# Mini-Coil_-_Signal_Board.net
KiCad netlist of a schematic drawn in Altium Designer
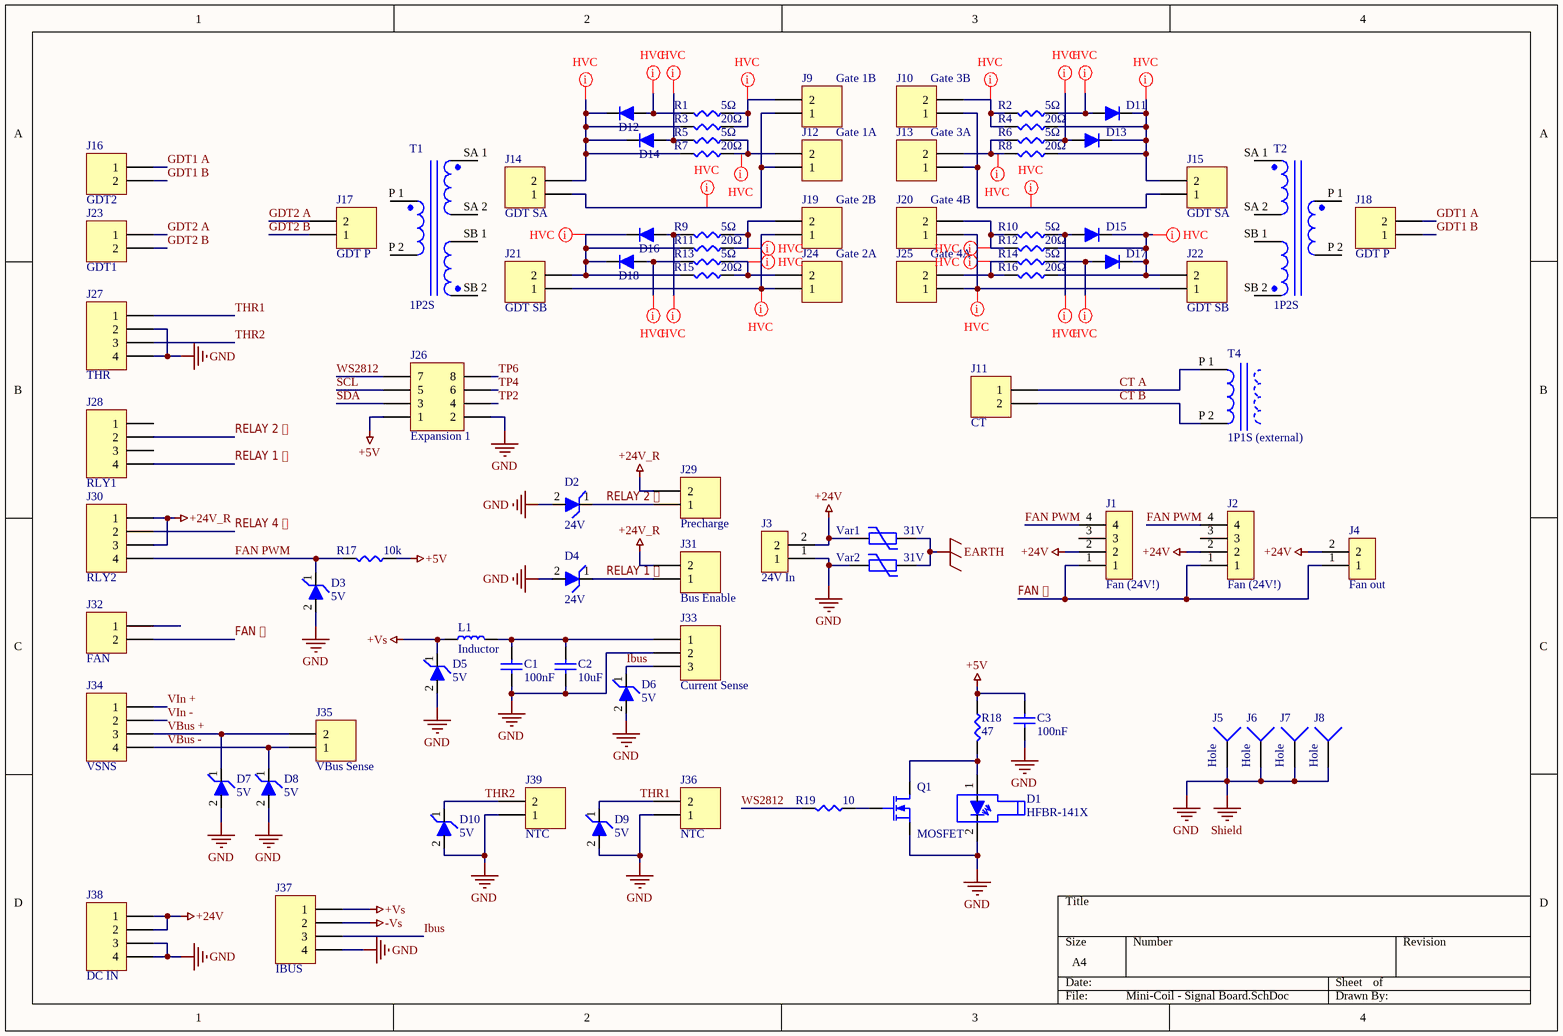
[diagram p0: Mini-Coil - Signal Board.SchDoc]

(export (version "E")
  (design (tool "Eeschema 10.0.6"))
  (components
    (comp (ref "C1") (value "100nF") (footprint "0603") (libsource (lib "stdLib") (part "Cap")))
    (comp (ref "C2") (value "10uF") (footprint "0603") (libsource (lib "stdLib") (part "Cap")))
    (comp (ref "C3") (value "100nF") (footprint "0603") (libsource (lib "stdLib") (part "Cap")))
    (comp (ref "D1")
      (value "HFBR-141X")
      (footprint "HFBR-X5XX")
      (description "Fiber optic transmitter. Click connector")
      (libsource (lib "stdLib") (part "HFBR-15XX Transmitter"))
    )
    (comp (ref "D2") (value "24V") (footprint "DO-214") (libsource (lib "stdLib") (part "TVS Diode")))
    (comp (ref "D3") (value "5V") (footprint "DO-214") (libsource (lib "stdLib") (part "TVS Diode")))
    (comp (ref "D4") (value "24V") (footprint "DO-214") (libsource (lib "stdLib") (part "TVS Diode")))
    (comp (ref "D5") (value "5V") (footprint "DO-214") (libsource (lib "stdLib") (part "TVS Diode")))
    (comp (ref "D6") (value "5V") (footprint "DO-214") (libsource (lib "stdLib") (part "TVS Diode")))
    (comp (ref "D7") (value "5V") (footprint "DO-214") (libsource (lib "stdLib") (part "TVS Diode")))
    (comp (ref "D8") (value "5V") (footprint "DO-214") (libsource (lib "stdLib") (part "TVS Diode")))
    (comp (ref "D9") (value "5V") (footprint "DO-214") (libsource (lib "stdLib") (part "TVS Diode")))
    (comp (ref "D10") (value "5V") (footprint "DO-214") (libsource (lib "stdLib") (part "TVS Diode")))
    (comp (ref "D11")
      (value "Diode")
      (footprint "DO-214")
      (description "Cmon its a diode what more do I need to say?")
      (libsource (lib "stdLib") (part "Diode"))
    )
    (comp (ref "D12")
      (value "Diode")
      (footprint "DO-214")
      (description "Cmon its a diode what more do I need to say?")
      (libsource (lib "stdLib") (part "Diode"))
    )
    (comp (ref "D13")
      (value "Diode")
      (footprint "DO-214")
      (description "Cmon its a diode what more do I need to say?")
      (libsource (lib "stdLib") (part "Diode"))
    )
    (comp (ref "D14")
      (value "Diode")
      (footprint "DO-214")
      (description "Cmon its a diode what more do I need to say?")
      (libsource (lib "stdLib") (part "Diode"))
    )
    (comp (ref "D15")
      (value "Diode")
      (footprint "DO-214")
      (description "Cmon its a diode what more do I need to say?")
      (libsource (lib "stdLib") (part "Diode"))
    )
    (comp (ref "D16")
      (value "Diode")
      (footprint "DO-214")
      (description "Cmon its a diode what more do I need to say?")
      (libsource (lib "stdLib") (part "Diode"))
    )
    (comp (ref "D17")
      (value "Diode")
      (footprint "DO-214")
      (description "Cmon its a diode what more do I need to say?")
      (libsource (lib "stdLib") (part "Diode"))
    )
    (comp (ref "D18")
      (value "Diode")
      (footprint "DO-214")
      (description "Cmon its a diode what more do I need to say?")
      (libsource (lib "stdLib") (part "Diode"))
    )
    (comp (ref "J1") (value "Fan (24V!)") (footprint "Fan 4Pin") (libsource (lib "stdCon") (part "4 header")))
    (comp (ref "J2") (value "Fan (24V!)") (footprint "Fan 4Pin") (libsource (lib "stdCon") (part "4 header")))
    (comp (ref "J3")
      (value "24V In")
      (footprint "2 screw terminal")
      (libsource (lib "stdCon") (part "2 screw terminal"))
    )
    (comp (ref "J4")
      (value "Fan out")
      (footprint "2 screw terminal")
      (libsource (lib "") (part "2 screw terminal_1"))
    )
    (comp (ref "J5")
      (value "Hole")
      (footprint "PIN1")
      (description "Socket")
      (fields (field (name "PUBLISHER") "Altium Limited"))
      (libsource (lib "Miscellaneous Connectors") (part "Socket"))
    )
    (comp (ref "J6")
      (value "Hole")
      (footprint "PIN1")
      (description "Socket")
      (fields (field (name "PUBLISHER") "Altium Limited"))
      (libsource (lib "Miscellaneous Connectors") (part "Socket"))
    )
    (comp (ref "J7")
      (value "Hole")
      (footprint "PIN1")
      (description "Socket")
      (fields (field (name "PUBLISHER") "Altium Limited"))
      (libsource (lib "Miscellaneous Connectors") (part "Socket"))
    )
    (comp (ref "J8")
      (value "Hole")
      (footprint "PIN1")
      (description "Socket")
      (fields (field (name "PUBLISHER") "Altium Limited"))
      (libsource (lib "Miscellaneous Connectors") (part "Socket"))
    )
    (comp (ref "J9")
      (value "Gate 1B")
      (footprint "HDR1X2")
      (description "Header, 2-Pin")
      (fields (field (name "PUBLISHER") "Altium Limited"))
      (libsource (lib "") (part "Header 2_1"))
    )
    (comp (ref "J10")
      (value "Gate 3B")
      (footprint "HDR1X2")
      (description "Header, 2-Pin")
      (fields (field (name "PUBLISHER") "Altium Limited"))
      (libsource (lib "Miscellaneous Connectors") (part "Header 2"))
    )
    (comp (ref "J11")
      (value "CT")
      (footprint "HDR1X2")
      (description "Header, 2-Pin")
      (fields (field (name "PUBLISHER") "Altium Limited"))
      (libsource (lib "") (part "Header 2_2"))
    )
    (comp (ref "J12")
      (value "Gate 1A")
      (footprint "HDR1X2")
      (description "Header, 2-Pin")
      (fields (field (name "PUBLISHER") "Altium Limited"))
      (libsource (lib "") (part "Header 2_1"))
    )
    (comp (ref "J13")
      (value "Gate 3A")
      (footprint "HDR1X2")
      (description "Header, 2-Pin")
      (fields (field (name "PUBLISHER") "Altium Limited"))
      (libsource (lib "Miscellaneous Connectors") (part "Header 2"))
    )
    (comp (ref "J14")
      (value "GDT SA")
      (footprint "2 KK254 / KF2510")
      (description "Header, 2-Pin")
      (fields (field (name "PUBLISHER") "Altium Limited"))
      (libsource (lib "Miscellaneous Connectors") (part "Header 2"))
    )
    (comp (ref "J15")
      (value "GDT SA")
      (footprint "2 KK254 / KF2510")
      (description "Header, 2-Pin")
      (fields (field (name "PUBLISHER") "Altium Limited"))
      (libsource (lib "") (part "Header 2_1"))
    )
    (comp (ref "J16")
      (value "GDT2")
      (footprint "HDR1X2")
      (description "Header, 2-Pin")
      (fields (field (name "PUBLISHER") "Altium Limited"))
      (libsource (lib "") (part "Header 2_2"))
    )
    (comp (ref "J17")
      (value "GDT P")
      (footprint "2 KK254 / KF2510")
      (description "Header, 2-Pin")
      (fields (field (name "PUBLISHER") "Altium Limited"))
      (libsource (lib "") (part "Header 2_1"))
    )
    (comp (ref "J18")
      (value "GDT P")
      (footprint "2 KK254 / KF2510")
      (description "Header, 2-Pin")
      (fields (field (name "PUBLISHER") "Altium Limited"))
      (libsource (lib "Miscellaneous Connectors") (part "Header 2"))
    )
    (comp (ref "J19")
      (value "Gate 2B")
      (footprint "HDR1X2")
      (description "Header, 2-Pin")
      (fields (field (name "PUBLISHER") "Altium Limited"))
      (libsource (lib "") (part "Header 2_1"))
    )
    (comp (ref "J20")
      (value "Gate 4B")
      (footprint "HDR1X2")
      (description "Header, 2-Pin")
      (fields (field (name "PUBLISHER") "Altium Limited"))
      (libsource (lib "Miscellaneous Connectors") (part "Header 2"))
    )
    (comp (ref "J21")
      (value "GDT SB")
      (footprint "2 KK254 / KF2510")
      (description "Header, 2-Pin")
      (fields (field (name "PUBLISHER") "Altium Limited"))
      (libsource (lib "Miscellaneous Connectors") (part "Header 2"))
    )
    (comp (ref "J22")
      (value "GDT SB")
      (footprint "2 KK254 / KF2510")
      (description "Header, 2-Pin")
      (fields (field (name "PUBLISHER") "Altium Limited"))
      (libsource (lib "") (part "Header 2_1"))
    )
    (comp (ref "J23")
      (value "GDT1")
      (footprint "HDR1X2")
      (description "Header, 2-Pin")
      (fields (field (name "PUBLISHER") "Altium Limited"))
      (libsource (lib "") (part "Header 2_2"))
    )
    (comp (ref "J24")
      (value "Gate 2A")
      (footprint "HDR1X2")
      (description "Header, 2-Pin")
      (fields (field (name "PUBLISHER") "Altium Limited"))
      (libsource (lib "") (part "Header 2_1"))
    )
    (comp (ref "J25")
      (value "Gate 4A")
      (footprint "HDR1X2")
      (description "Header, 2-Pin")
      (fields (field (name "PUBLISHER") "Altium Limited"))
      (libsource (lib "Miscellaneous Connectors") (part "Header 2"))
    )
    (comp (ref "J26")
      (value "Expansion 1")
      (footprint "HDR2X4")
      (description "Header, 4-Pin, Dual row")
      (fields (field (name "PUBLISHER") "Altium Limited"))
      (libsource (lib "Miscellaneous Connectors") (part "Header 4X2"))
    )
    (comp (ref "J27")
      (value "THR")
      (footprint "HDR1X4")
      (description "Header, 4-Pin")
      (fields (field (name "PUBLISHER") "Altium Limited"))
      (libsource (lib "Miscellaneous Connectors") (part "Header 4"))
    )
    (comp (ref "J28")
      (value "RLY1")
      (footprint "HDR1X4")
      (description "Header, 4-Pin")
      (fields (field (name "PUBLISHER") "Altium Limited"))
      (libsource (lib "Miscellaneous Connectors") (part "Header 4"))
    )
    (comp (ref "J29")
      (value "Precharge")
      (footprint "HDR1X2")
      (description "Header, 2-Pin")
      (fields (field (name "PUBLISHER") "Altium Limited"))
      (libsource (lib "") (part "Header 2_1"))
    )
    (comp (ref "J30")
      (value "RLY2")
      (footprint "HDR1X4")
      (description "Header, 4-Pin")
      (fields (field (name "PUBLISHER") "Altium Limited"))
      (libsource (lib "Miscellaneous Connectors") (part "Header 4"))
    )
    (comp (ref "J31")
      (value "Bus Enable")
      (footprint "HDR1X2")
      (description "Header, 2-Pin")
      (fields (field (name "PUBLISHER") "Altium Limited"))
      (libsource (lib "") (part "Header 2_1"))
    )
    (comp (ref "J32")
      (value "FAN")
      (footprint "HDR1X2")
      (description "Header, 2-Pin")
      (fields (field (name "PUBLISHER") "Altium Limited"))
      (libsource (lib "") (part "Header 2_2"))
    )
    (comp (ref "J33")
      (value "Current Sense")
      (footprint "HDR1X3")
      (description "Header, 3-Pin")
      (fields (field (name "PUBLISHER") "Altium Limited"))
      (libsource (lib "Miscellaneous Connectors") (part "Header 3"))
    )
    (comp (ref "J34")
      (value "VSNS")
      (footprint "HDR1X4")
      (description "Header, 4-Pin")
      (fields (field (name "PUBLISHER") "Altium Limited"))
      (libsource (lib "Miscellaneous Connectors") (part "Header 4"))
    )
    (comp (ref "J35")
      (value "VBus Sense")
      (footprint "HDR1X2")
      (description "Header, 2-Pin")
      (fields (field (name "PUBLISHER") "Altium Limited"))
      (libsource (lib "") (part "Header 2_1"))
    )
    (comp (ref "J36")
      (value "NTC")
      (footprint "HDR1X2")
      (description "Header, 2-Pin")
      (fields (field (name "PUBLISHER") "Altium Limited"))
      (libsource (lib "") (part "Header 2_1"))
    )
    (comp (ref "J37")
      (value "IBUS")
      (footprint "HDR1X4")
      (description "Header, 4-Pin")
      (fields (field (name "PUBLISHER") "Altium Limited"))
      (libsource (lib "Miscellaneous Connectors") (part "Header 4"))
    )
    (comp (ref "J38")
      (value "DC IN")
      (footprint "HDR1X4")
      (description "Header, 4-Pin")
      (fields (field (name "PUBLISHER") "Altium Limited"))
      (libsource (lib "Miscellaneous Connectors") (part "Header 4"))
    )
    (comp (ref "J39")
      (value "NTC")
      (footprint "HDR1X2")
      (description "Header, 2-Pin")
      (fields (field (name "PUBLISHER") "Altium Limited"))
      (libsource (lib "") (part "Header 2_1"))
    )
    (comp (ref "L1") (value "Inductor") (footprint "0603") (libsource (lib "stdLib") (part "Inductor")))
    (comp (ref "Q1") (value "MOSFET") (footprint "sot 23") (libsource (lib "stdLib") (part "Mosfet N")))
    (comp (ref "R1") (value "5Ω") (footprint "2512") (libsource (lib "stdLib") (part "Resistor")))
    (comp (ref "R2") (value "5Ω") (footprint "2512") (libsource (lib "stdLib") (part "Resistor")))
    (comp (ref "R3") (value "20Ω") (footprint "2512") (libsource (lib "stdLib") (part "Resistor")))
    (comp (ref "R4") (value "20Ω") (footprint "2512") (libsource (lib "stdLib") (part "Resistor")))
    (comp (ref "R5") (value "5Ω") (footprint "2512") (libsource (lib "stdLib") (part "Resistor")))
    (comp (ref "R6") (value "5Ω") (footprint "2512") (libsource (lib "stdLib") (part "Resistor")))
    (comp (ref "R7") (value "20Ω") (footprint "2512") (libsource (lib "stdLib") (part "Resistor")))
    (comp (ref "R8") (value "20Ω") (footprint "2512") (libsource (lib "stdLib") (part "Resistor")))
    (comp (ref "R9") (value "5Ω") (footprint "2512") (libsource (lib "stdLib") (part "Resistor")))
    (comp (ref "R10") (value "5Ω") (footprint "2512") (libsource (lib "stdLib") (part "Resistor")))
    (comp (ref "R11") (value "20Ω") (footprint "2512") (libsource (lib "stdLib") (part "Resistor")))
    (comp (ref "R12") (value "20Ω") (footprint "2512") (libsource (lib "stdLib") (part "Resistor")))
    (comp (ref "R13") (value "5Ω") (footprint "2512") (libsource (lib "stdLib") (part "Resistor")))
    (comp (ref "R14") (value "5Ω") (footprint "2512") (libsource (lib "stdLib") (part "Resistor")))
    (comp (ref "R15") (value "20Ω") (footprint "2512") (libsource (lib "stdLib") (part "Resistor")))
    (comp (ref "R16") (value "20Ω") (footprint "2512") (libsource (lib "stdLib") (part "Resistor")))
    (comp (ref "R17") (value "10k") (footprint "0603") (libsource (lib "stdLib") (part "Resistor")))
    (comp (ref "R18") (value "47") (footprint "0603") (libsource (lib "stdLib") (part "Resistor")))
    (comp (ref "R19") (value "10") (footprint "0603") (libsource (lib "stdLib") (part "Resistor")))
    (comp (ref "T1") (value "1P2S") (footprint "GDT Toroidal") (libsource (lib "") (part "1P2S_1")))
    (comp (ref "T2") (value "1P2S") (footprint "GDT Toroidal") (libsource (lib "Transformers") (part "1P2S")))
    (comp (ref "T4")
      (value "1P1S (external)")
      (footprint "Current-Sense Toroid, Vertical")
      (description "Transformer with Secondary winding connected externally")
      (libsource (lib "Transformers") (part "1P1S (external)"))
    )
    (comp (ref "Var1")
      (value "31V")
      (footprint "Varistor disc 7mm")
      (description "Varistor, he protecc")
      (libsource (lib "stdLib") (part "Varistor"))
    )
    (comp (ref "Var2")
      (value "31V")
      (footprint "Varistor disc 7mm")
      (description "Varistor, he protecc")
      (libsource (lib "stdLib") (part "Varistor"))
    )
  )
  (nets
    (net (code "1") (name "+5V") (class "Default")
      (node (ref "C3") (pin "2") (pinfunction "2_2") (pintype "passive"))
      (node (ref "J26") (pin "1") (pinfunction "1_1") (pintype "passive"))
      (node (ref "R17") (pin "1") (pinfunction "1_1") (pintype "passive"))
      (node (ref "R18") (pin "1") (pinfunction "1_1") (pintype "passive"))
    )
    (net (code "2") (name "+24V") (class "Default")
      (node (ref "J1") (pin "2") (pinfunction "2_2") (pintype "passive"))
      (node (ref "J2") (pin "2") (pinfunction "2_2") (pintype "passive"))
      (node (ref "J3") (pin "2") (pinfunction "2_2") (pintype "passive"))
      (node (ref "J38") (pin "1") (pinfunction "1_1") (pintype "passive"))
      (node (ref "J38") (pin "2") (pinfunction "2_2") (pintype "passive"))
      (node (ref "J4") (pin "2") (pinfunction "2_2") (pintype "passive"))
      (node (ref "Var1") (pin "2") (pinfunction "2_2") (pintype "passive"))
    )
    (net (code "3") (name "+24V_R") (class "Default")
      (node (ref "J29") (pin "2") (pinfunction "2_2") (pintype "passive"))
      (node (ref "J30") (pin "1") (pinfunction "1_1") (pintype "passive"))
      (node (ref "J30") (pin "3") (pinfunction "3_3") (pintype "passive"))
      (node (ref "J31") (pin "2") (pinfunction "2_2") (pintype "passive"))
    )
    (net (code "4") (name "+Vs") (class "Default")
      (node (ref "D5") (pin "1") (pintype "passive"))
      (node (ref "J37") (pin "1") (pinfunction "1_1") (pintype "passive"))
      (node (ref "L1") (pin "1") (pinfunction "1_1") (pintype "passive"))
    )
    (net (code "5") (name "-Vs") (class "Default")
      (node (ref "J37") (pin "2") (pinfunction "2_2") (pintype "passive"))
    )
    (net (code "6") (name "/CT A") (class "Default")
      (node (ref "J11") (pin "1") (pinfunction "1_1") (pintype "passive"))
      (node (ref "T4") (pin "P_1") (pinfunction "7_P_1") (pintype "passive"))
    )
    (net (code "7") (name "/CT B") (class "Default")
      (node (ref "J11") (pin "2") (pinfunction "2_2") (pintype "passive"))
      (node (ref "T4") (pin "P_2") (pinfunction "6_P_2") (pintype "passive"))
    )
    (net (code "8") (name "/FAN PWM") (class "Default")
      (node (ref "D3") (pin "1") (pintype "passive"))
      (node (ref "J1") (pin "4") (pinfunction "4_4") (pintype "passive"))
      (node (ref "J2") (pin "4") (pinfunction "4_4") (pintype "passive"))
      (node (ref "J30") (pin "4") (pinfunction "4_4") (pintype "passive"))
      (node (ref "R17") (pin "2") (pinfunction "2_2") (pintype "passive"))
    )
    (net (code "9") (name "/FAN ⎐") (class "Default")
      (node (ref "J1") (pin "1") (pinfunction "1_1") (pintype "passive"))
      (node (ref "J2") (pin "1") (pinfunction "1_1") (pintype "passive"))
      (node (ref "J32") (pin "2") (pinfunction "2_2") (pintype "passive"))
      (node (ref "J4") (pin "1") (pinfunction "1_1") (pintype "passive"))
    )
    (net (code "10") (name "/GDT1 A") (class "Default")
      (node (ref "J16") (pin "1") (pinfunction "1_1") (pintype "passive"))
      (node (ref "J18") (pin "2") (pinfunction "2_2") (pintype "passive"))
    )
    (net (code "11") (name "/GDT1 B") (class "Default")
      (node (ref "J16") (pin "2") (pinfunction "2_2") (pintype "passive"))
      (node (ref "J18") (pin "1") (pinfunction "1_1") (pintype "passive"))
    )
    (net (code "12") (name "/GDT2 A") (class "Default")
      (node (ref "J17") (pin "2") (pinfunction "2_2") (pintype "passive"))
      (node (ref "J23") (pin "1") (pinfunction "1_1") (pintype "passive"))
    )
    (net (code "13") (name "/GDT2 B") (class "Default")
      (node (ref "J17") (pin "1") (pinfunction "1_1") (pintype "passive"))
      (node (ref "J23") (pin "2") (pinfunction "2_2") (pintype "passive"))
    )
    (net (code "14") (name "/Ibus") (class "Default")
      (node (ref "D6") (pin "1") (pintype "passive"))
      (node (ref "J33") (pin "3") (pinfunction "3_3") (pintype "passive"))
      (node (ref "J37") (pin "3") (pinfunction "3_3") (pintype "passive"))
    )
    (net (code "15") (name "/RELAY 1 ⎐") (class "Default")
      (node (ref "D4") (pin "1") (pintype "passive"))
      (node (ref "J28") (pin "4") (pinfunction "4_4") (pintype "passive"))
      (node (ref "J31") (pin "1") (pinfunction "1_1") (pintype "passive"))
    )
    (net (code "16") (name "/RELAY 2 ⎐") (class "Default")
      (node (ref "D2") (pin "1") (pintype "passive"))
      (node (ref "J28") (pin "2") (pinfunction "2_2") (pintype "passive"))
      (node (ref "J29") (pin "1") (pinfunction "1_1") (pintype "passive"))
    )
    (net (code "17") (name "/RELAY 4 ⎐") (class "Default")
      (node (ref "J30") (pin "2") (pinfunction "2_2") (pintype "passive"))
    )
    (net (code "18") (name "/SCL") (class "Default")
      (node (ref "J26") (pin "5") (pinfunction "5_5") (pintype "passive"))
    )
    (net (code "19") (name "/SDA") (class "Default")
      (node (ref "J26") (pin "3") (pinfunction "3_3") (pintype "passive"))
    )
    (net (code "20") (name "/THR1") (class "Default")
      (node (ref "D9") (pin "1") (pintype "passive"))
      (node (ref "J27") (pin "1") (pinfunction "1_1") (pintype "passive"))
      (node (ref "J36") (pin "2") (pinfunction "2_2") (pintype "passive"))
    )
    (net (code "21") (name "/THR2") (class "Default")
      (node (ref "D10") (pin "1") (pintype "passive"))
      (node (ref "J27") (pin "3") (pinfunction "3_3") (pintype "passive"))
      (node (ref "J39") (pin "2") (pinfunction "2_2") (pintype "passive"))
    )
    (net (code "22") (name "/TP2") (class "Default")
      (node (ref "J26") (pin "4") (pinfunction "4_4") (pintype "passive"))
    )
    (net (code "23") (name "/TP4") (class "Default")
      (node (ref "J26") (pin "6") (pinfunction "6_6") (pintype "passive"))
    )
    (net (code "24") (name "/TP6") (class "Default")
      (node (ref "J26") (pin "8") (pinfunction "8_8") (pintype "passive"))
    )
    (net (code "25") (name "/VBus +") (class "Default")
      (node (ref "D7") (pin "1") (pintype "passive"))
      (node (ref "J34") (pin "3") (pinfunction "3_3") (pintype "passive"))
      (node (ref "J35") (pin "2") (pinfunction "2_2") (pintype "passive"))
    )
    (net (code "26") (name "/VBus -") (class "Default")
      (node (ref "D8") (pin "1") (pintype "passive"))
      (node (ref "J34") (pin "4") (pinfunction "4_4") (pintype "passive"))
      (node (ref "J35") (pin "1") (pinfunction "1_1") (pintype "passive"))
    )
    (net (code "27") (name "/VIn +") (class "Default")
      (node (ref "J34") (pin "1") (pinfunction "1_1") (pintype "passive"))
    )
    (net (code "28") (name "/VIn -") (class "Default")
      (node (ref "J34") (pin "2") (pinfunction "2_2") (pintype "passive"))
    )
    (net (code "29") (name "/WS2812") (class "Default")
      (node (ref "J26") (pin "7") (pinfunction "7_7") (pintype "passive"))
      (node (ref "R19") (pin "2") (pinfunction "2_2") (pintype "passive"))
    )
    (net (code "30") (name "EARTH") (class "Default")
      (node (ref "Var1") (pin "1") (pinfunction "1_1") (pintype "passive"))
      (node (ref "Var2") (pin "1") (pinfunction "1_1") (pintype "passive"))
    )
    (net (code "31") (name "GND") (class "Default")
      (node (ref "C1") (pin "1") (pinfunction "1_1") (pintype "passive"))
      (node (ref "C2") (pin "1") (pinfunction "1_1") (pintype "passive"))
      (node (ref "C3") (pin "1") (pinfunction "1_1") (pintype "passive"))
      (node (ref "D1") (pin "2") (pintype "passive"))
      (node (ref "D10") (pin "2") (pintype "passive"))
      (node (ref "D2") (pin "2") (pintype "passive"))
      (node (ref "D3") (pin "2") (pintype "passive"))
      (node (ref "D4") (pin "2") (pintype "passive"))
      (node (ref "D5") (pin "2") (pintype "passive"))
      (node (ref "D6") (pin "2") (pintype "passive"))
      (node (ref "D7") (pin "2") (pintype "passive"))
      (node (ref "D8") (pin "2") (pintype "passive"))
      (node (ref "D9") (pin "2") (pintype "passive"))
      (node (ref "J26") (pin "2") (pinfunction "2_2") (pintype "passive"))
      (node (ref "J27") (pin "2") (pinfunction "2_2") (pintype "passive"))
      (node (ref "J27") (pin "4") (pinfunction "4_4") (pintype "passive"))
      (node (ref "J3") (pin "1") (pinfunction "1_1") (pintype "passive"))
      (node (ref "J33") (pin "2") (pinfunction "2_2") (pintype "passive"))
      (node (ref "J36") (pin "1") (pinfunction "1_1") (pintype "passive"))
      (node (ref "J37") (pin "4") (pinfunction "4_4") (pintype "passive"))
      (node (ref "J38") (pin "3") (pinfunction "3_3") (pintype "passive"))
      (node (ref "J38") (pin "4") (pinfunction "4_4") (pintype "passive"))
      (node (ref "J39") (pin "1") (pinfunction "1_1") (pintype "passive"))
      (node (ref "J5") (pin "1") (pinfunction "1_1") (pintype "passive"))
      (node (ref "J6") (pin "1") (pinfunction "1_1") (pintype "passive"))
      (node (ref "J7") (pin "1") (pinfunction "1_1") (pintype "passive"))
      (node (ref "J8") (pin "1") (pinfunction "1_1") (pintype "passive"))
      (node (ref "Q1") (pin "S") (pinfunction "S_S") (pintype "passive"))
      (node (ref "Var2") (pin "2") (pinfunction "2_2") (pintype "passive"))
    )
    (net (code "32") (name "Net-(C1-Pad2)") (class "Default")
      (node (ref "C1") (pin "2") (pinfunction "2_2") (pintype "passive"))
      (node (ref "C2") (pin "2") (pinfunction "2_2") (pintype "passive"))
      (node (ref "J33") (pin "1") (pinfunction "1_1") (pintype "passive"))
      (node (ref "L1") (pin "2") (pinfunction "2_2") (pintype "passive"))
    )
    (net (code "33") (name "Net-(D1-Pad1)") (class "Default")
      (node (ref "D1") (pin "1") (pintype "passive"))
      (node (ref "Q1") (pin "D") (pinfunction "D_D") (pintype "passive"))
      (node (ref "R18") (pin "2") (pinfunction "2_2") (pintype "passive"))
    )
    (net (code "34") (name "Net-(D11-Pad1)") (class "Default")
      (node (ref "D11") (pin "1") (pintype "passive"))
      (node (ref "R2") (pin "2") (pinfunction "2_2") (pintype "passive"))
    )
    (net (code "35") (name "Net-(D11-Pad2)") (class "Default")
      (node (ref "D11") (pin "2") (pintype "passive"))
      (node (ref "D13") (pin "2") (pintype "passive"))
      (node (ref "J15") (pin "2") (pinfunction "2_2") (pintype "passive"))
      (node (ref "R4") (pin "2") (pinfunction "2_2") (pintype "passive"))
      (node (ref "R8") (pin "2") (pinfunction "2_2") (pintype "passive"))
    )
    (net (code "36") (name "Net-(D12-Pad1)") (class "Default")
      (node (ref "D12") (pin "1") (pintype "passive"))
      (node (ref "R1") (pin "2") (pinfunction "2_2") (pintype "passive"))
    )
    (net (code "37") (name "Net-(D12-Pad2)") (class "Default")
      (node (ref "D12") (pin "2") (pintype "passive"))
      (node (ref "D14") (pin "2") (pintype "passive"))
      (node (ref "J14") (pin "2") (pinfunction "2_2") (pintype "passive"))
      (node (ref "R3") (pin "2") (pinfunction "2_2") (pintype "passive"))
      (node (ref "R7") (pin "2") (pinfunction "2_2") (pintype "passive"))
    )
    (net (code "38") (name "Net-(D13-Pad1)") (class "Default")
      (node (ref "D13") (pin "1") (pintype "passive"))
      (node (ref "R6") (pin "2") (pinfunction "2_2") (pintype "passive"))
    )
    (net (code "39") (name "Net-(D14-Pad1)") (class "Default")
      (node (ref "D14") (pin "1") (pintype "passive"))
      (node (ref "R5") (pin "2") (pinfunction "2_2") (pintype "passive"))
    )
    (net (code "40") (name "Net-(D15-Pad1)") (class "Default")
      (node (ref "D15") (pin "1") (pintype "passive"))
      (node (ref "R10") (pin "2") (pinfunction "2_2") (pintype "passive"))
    )
    (net (code "41") (name "Net-(D15-Pad2)") (class "Default")
      (node (ref "D15") (pin "2") (pintype "passive"))
      (node (ref "D17") (pin "2") (pintype "passive"))
      (node (ref "J22") (pin "2") (pinfunction "2_2") (pintype "passive"))
      (node (ref "R12") (pin "2") (pinfunction "2_2") (pintype "passive"))
      (node (ref "R16") (pin "2") (pinfunction "2_2") (pintype "passive"))
    )
    (net (code "42") (name "Net-(D16-Pad1)") (class "Default")
      (node (ref "D16") (pin "1") (pintype "passive"))
      (node (ref "R9") (pin "2") (pinfunction "2_2") (pintype "passive"))
    )
    (net (code "43") (name "Net-(D16-Pad2)") (class "Default")
      (node (ref "D16") (pin "2") (pintype "passive"))
      (node (ref "D18") (pin "2") (pintype "passive"))
      (node (ref "J21") (pin "2") (pinfunction "2_2") (pintype "passive"))
      (node (ref "R11") (pin "2") (pinfunction "2_2") (pintype "passive"))
      (node (ref "R15") (pin "2") (pinfunction "2_2") (pintype "passive"))
    )
    (net (code "44") (name "Net-(D17-Pad1)") (class "Default")
      (node (ref "D17") (pin "1") (pintype "passive"))
      (node (ref "R14") (pin "2") (pinfunction "2_2") (pintype "passive"))
    )
    (net (code "45") (name "Net-(D18-Pad1)") (class "Default")
      (node (ref "D18") (pin "1") (pintype "passive"))
      (node (ref "R13") (pin "2") (pinfunction "2_2") (pintype "passive"))
    )
    (net (code "46") (name "Net-(J9-Pad2)") (class "Default")
      (node (ref "J9") (pin "2") (pinfunction "2_2") (pintype "passive"))
      (node (ref "R1") (pin "1") (pinfunction "1_1") (pintype "passive"))
      (node (ref "R3") (pin "1") (pinfunction "1_1") (pintype "passive"))
    )
    (net (code "47") (name "Net-(J10-Pad1)") (class "Default")
      (node (ref "J10") (pin "1") (pinfunction "1_1") (pintype "passive"))
      (node (ref "J13") (pin "1") (pinfunction "1_1") (pintype "passive"))
      (node (ref "J15") (pin "1") (pinfunction "1_1") (pintype "passive"))
    )
    (net (code "48") (name "Net-(J10-Pad2)") (class "Default")
      (node (ref "J10") (pin "2") (pinfunction "2_2") (pintype "passive"))
      (node (ref "R2") (pin "1") (pinfunction "1_1") (pintype "passive"))
      (node (ref "R4") (pin "1") (pinfunction "1_1") (pintype "passive"))
    )
    (net (code "49") (name "Net-(J12-Pad1)") (class "Default")
      (node (ref "J12") (pin "1") (pinfunction "1_1") (pintype "passive"))
      (node (ref "J14") (pin "1") (pinfunction "1_1") (pintype "passive"))
      (node (ref "J9") (pin "1") (pinfunction "1_1") (pintype "passive"))
    )
    (net (code "50") (name "Net-(J12-Pad2)") (class "Default")
      (node (ref "J12") (pin "2") (pinfunction "2_2") (pintype "passive"))
      (node (ref "R5") (pin "1") (pinfunction "1_1") (pintype "passive"))
      (node (ref "R7") (pin "1") (pinfunction "1_1") (pintype "passive"))
    )
    (net (code "51") (name "Net-(J13-Pad2)") (class "Default")
      (node (ref "J13") (pin "2") (pinfunction "2_2") (pintype "passive"))
      (node (ref "R6") (pin "1") (pinfunction "1_1") (pintype "passive"))
      (node (ref "R8") (pin "1") (pinfunction "1_1") (pintype "passive"))
    )
    (net (code "52") (name "Net-(J19-Pad1)") (class "Default")
      (node (ref "J19") (pin "1") (pinfunction "1_1") (pintype "passive"))
      (node (ref "J21") (pin "1") (pinfunction "1_1") (pintype "passive"))
      (node (ref "J24") (pin "1") (pinfunction "1_1") (pintype "passive"))
    )
    (net (code "53") (name "Net-(J19-Pad2)") (class "Default")
      (node (ref "J19") (pin "2") (pinfunction "2_2") (pintype "passive"))
      (node (ref "R11") (pin "1") (pinfunction "1_1") (pintype "passive"))
      (node (ref "R9") (pin "1") (pinfunction "1_1") (pintype "passive"))
    )
    (net (code "54") (name "Net-(J20-Pad1)") (class "Default")
      (node (ref "J20") (pin "1") (pinfunction "1_1") (pintype "passive"))
      (node (ref "J22") (pin "1") (pinfunction "1_1") (pintype "passive"))
      (node (ref "J25") (pin "1") (pinfunction "1_1") (pintype "passive"))
    )
    (net (code "55") (name "Net-(J20-Pad2)") (class "Default")
      (node (ref "J20") (pin "2") (pinfunction "2_2") (pintype "passive"))
      (node (ref "R10") (pin "1") (pinfunction "1_1") (pintype "passive"))
      (node (ref "R12") (pin "1") (pinfunction "1_1") (pintype "passive"))
    )
    (net (code "56") (name "Net-(J24-Pad2)") (class "Default")
      (node (ref "J24") (pin "2") (pinfunction "2_2") (pintype "passive"))
      (node (ref "R13") (pin "1") (pinfunction "1_1") (pintype "passive"))
      (node (ref "R15") (pin "1") (pinfunction "1_1") (pintype "passive"))
    )
    (net (code "57") (name "Net-(J25-Pad2)") (class "Default")
      (node (ref "J25") (pin "2") (pinfunction "2_2") (pintype "passive"))
      (node (ref "R14") (pin "1") (pinfunction "1_1") (pintype "passive"))
      (node (ref "R16") (pin "1") (pinfunction "1_1") (pintype "passive"))
    )
    (net (code "58") (name "Net-(Q1-PadG)") (class "Default")
      (node (ref "Q1") (pin "G") (pinfunction "G_G") (pintype "passive"))
      (node (ref "R19") (pin "1") (pinfunction "1_1") (pintype "passive"))
    )
    (net (code "59") (name "unconnected-(J1-Pad3)") (class "Default")
      (node (ref "J1") (pin "3") (pinfunction "3_3") (pintype "passive"))
    )
    (net (code "60") (name "unconnected-(J2-Pad3)") (class "Default")
      (node (ref "J2") (pin "3") (pinfunction "3_3") (pintype "passive"))
    )
    (net (code "61") (name "unconnected-(J28-Pad1)") (class "Default")
      (node (ref "J28") (pin "1") (pinfunction "1_1") (pintype "passive"))
    )
    (net (code "62") (name "unconnected-(J28-Pad3)") (class "Default")
      (node (ref "J28") (pin "3") (pinfunction "3_3") (pintype "passive"))
    )
    (net (code "63") (name "unconnected-(J32-Pad1)") (class "Default")
      (node (ref "J32") (pin "1") (pinfunction "1_1") (pintype "passive"))
    )
    (net (code "64") (name "unconnected-(T1-0-PadSA_1)") (class "Default")
      (node (ref "T1") (pin "SA_1") (pinfunction "0_SA_1") (pintype "passive"))
    )
    (net (code "65") (name "unconnected-(T1-1-PadSA_2)") (class "Default")
      (node (ref "T1") (pin "SA_2") (pinfunction "1_SA_2") (pintype "passive"))
    )
    (net (code "66") (name "unconnected-(T1-2-PadSB_1)") (class "Default")
      (node (ref "T1") (pin "SB_1") (pinfunction "2_SB_1") (pintype "passive"))
    )
    (net (code "67") (name "unconnected-(T1-3-PadSB_2)") (class "Default")
      (node (ref "T1") (pin "SB_2") (pinfunction "3_SB_2") (pintype "passive"))
    )
    (net (code "68") (name "unconnected-(T1-6-PadP_2)") (class "Default")
      (node (ref "T1") (pin "P_2") (pinfunction "6_P_2") (pintype "passive"))
    )
    (net (code "69") (name "unconnected-(T1-7-PadP_1)") (class "Default")
      (node (ref "T1") (pin "P_1") (pinfunction "7_P_1") (pintype "passive"))
    )
    (net (code "70") (name "unconnected-(T2-0-PadSA_1)") (class "Default")
      (node (ref "T2") (pin "SA_1") (pinfunction "0_SA_1") (pintype "passive"))
    )
    (net (code "71") (name "unconnected-(T2-1-PadSA_2)") (class "Default")
      (node (ref "T2") (pin "SA_2") (pinfunction "1_SA_2") (pintype "passive"))
    )
    (net (code "72") (name "unconnected-(T2-2-PadSB_1)") (class "Default")
      (node (ref "T2") (pin "SB_1") (pinfunction "2_SB_1") (pintype "passive"))
    )
    (net (code "73") (name "unconnected-(T2-3-PadSB_2)") (class "Default")
      (node (ref "T2") (pin "SB_2") (pinfunction "3_SB_2") (pintype "passive"))
    )
    (net (code "74") (name "unconnected-(T2-6-PadP_2)") (class "Default")
      (node (ref "T2") (pin "P_2") (pinfunction "6_P_2") (pintype "passive"))
    )
    (net (code "75") (name "unconnected-(T2-7-PadP_1)") (class "Default")
      (node (ref "T2") (pin "P_1") (pinfunction "7_P_1") (pintype "passive"))
    )
  )
)
